# SparkFun_Optical_Tracking_Odometry_Senso.net
KiCad netlist of a schematic drawn in EAGLE
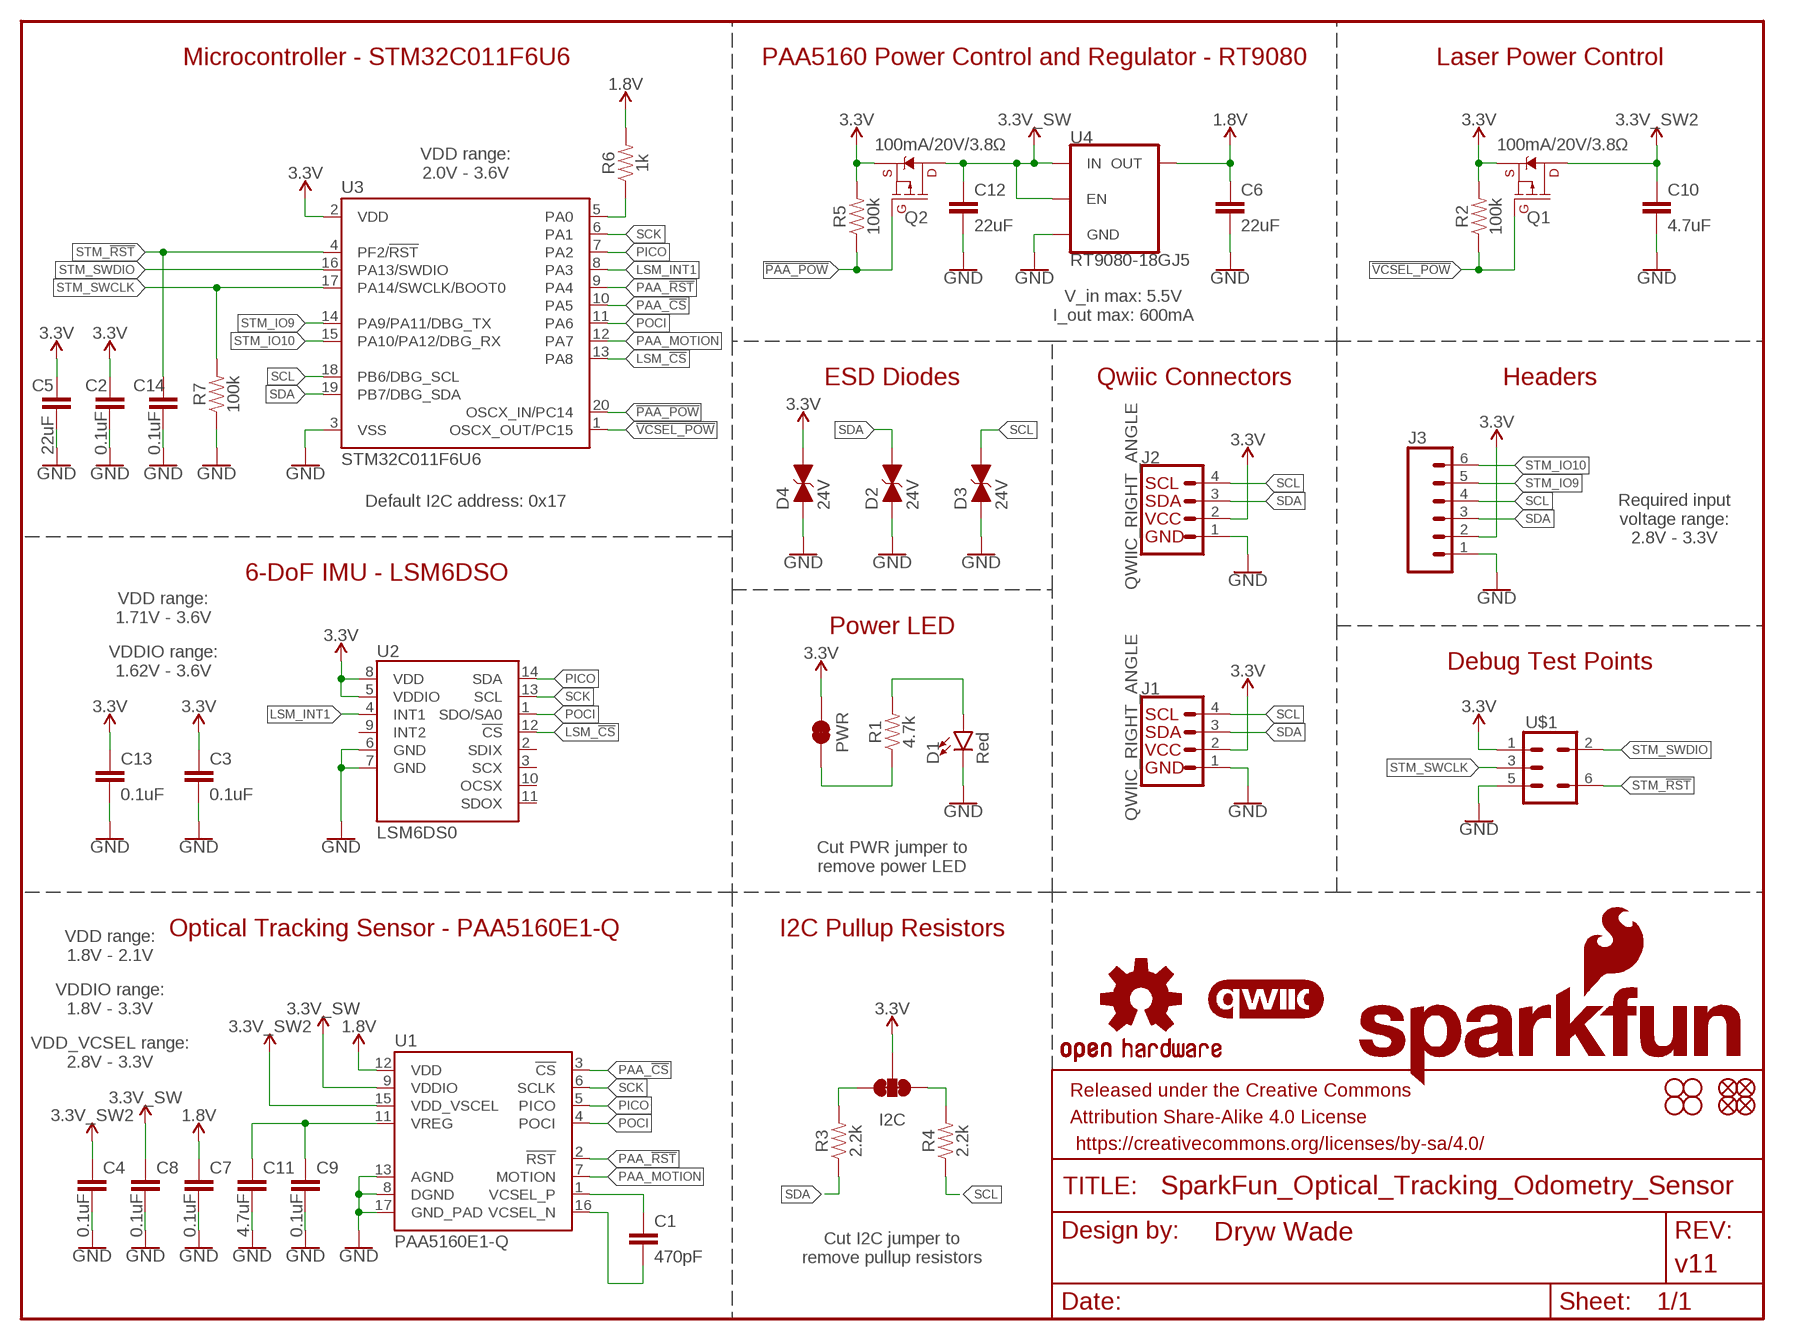
[diagram p0: schematic, sheet 1]

(export (version "E")
  (design (tool "Eeschema 10.0.6"))
  (components
    (comp (ref "C1")
      (value "470pF")
      (footprint "eagle-import:0603")
      (libsource (lib "eagle-import") (part "470PF-0603-50V-5%"))
    )
    (comp (ref "C2")
      (value "0.1uF")
      (footprint "eagle-import:0603")
      (libsource (lib "eagle-import") (part "0.1UF-0603-25V-(+80/-20%)"))
    )
    (comp (ref "C3")
      (value "0.1uF")
      (footprint "eagle-import:0603")
      (libsource (lib "eagle-import") (part "0.1UF-0603-25V-(+80/-20%)"))
    )
    (comp (ref "C4")
      (value "0.1uF")
      (footprint "eagle-import:0603")
      (libsource (lib "eagle-import") (part "0.1UF-0603-25V-(+80/-20%)"))
    )
    (comp (ref "C5")
      (value "22uF")
      (footprint "eagle-import:0603")
      (libsource (lib "eagle-import") (part "22UF-0603-6.3V-20%"))
    )
    (comp (ref "C6")
      (value "22uF")
      (footprint "eagle-import:0603")
      (libsource (lib "eagle-import") (part "22UF-0603-6.3V-20%"))
    )
    (comp (ref "C7")
      (value "0.1uF")
      (footprint "eagle-import:0603")
      (libsource (lib "eagle-import") (part "0.1UF-0603-25V-(+80/-20%)"))
    )
    (comp (ref "C8")
      (value "0.1uF")
      (footprint "eagle-import:0603")
      (libsource (lib "eagle-import") (part "0.1UF-0603-25V-(+80/-20%)"))
    )
    (comp (ref "C9")
      (value "0.1uF")
      (footprint "eagle-import:0603")
      (libsource (lib "eagle-import") (part "0.1UF-0603-25V-(+80/-20%)"))
    )
    (comp (ref "C10")
      (value "4.7uF")
      (footprint "eagle-import:0603")
      (libsource (lib "eagle-import") (part "4.7UF-0603-6.3V-(10%)"))
    )
    (comp (ref "C11")
      (value "4.7uF")
      (footprint "eagle-import:0603")
      (libsource (lib "eagle-import") (part "4.7UF-0603-6.3V-(10%)"))
    )
    (comp (ref "C12")
      (value "22uF")
      (footprint "eagle-import:0603")
      (libsource (lib "eagle-import") (part "22UF-0603-6.3V-20%"))
    )
    (comp (ref "C13")
      (value "0.1uF")
      (footprint "eagle-import:0603")
      (libsource (lib "eagle-import") (part "0.1UF-0603-25V-(+80/-20%)"))
    )
    (comp (ref "C14")
      (value "0.1uF")
      (footprint "eagle-import:0603")
      (libsource (lib "eagle-import") (part "0.1UF-0603-25V-(+80/-20%)"))
    )
    (comp (ref "D1")
      (value "Red")
      (footprint "eagle-import:LED-0603")
      (libsource (lib "eagle-import") (part "LED-RED_0603-KB"))
    )
    (comp (ref "D2")
      (value "24V")
      (footprint "eagle-import:0603")
      (libsource (lib "eagle-import") (part "DIODE_TVS"))
    )
    (comp (ref "D3")
      (value "24V")
      (footprint "eagle-import:0603")
      (libsource (lib "eagle-import") (part "DIODE_TVS"))
    )
    (comp (ref "D4")
      (value "24V")
      (footprint "eagle-import:0603")
      (libsource (lib "eagle-import") (part "DIODE_TVS"))
    )
    (comp (ref "FD1")
      (value "FIDUCIAL1X2")
      (footprint "eagle-import:FIDUCIAL-1X2")
      (libsource (lib "eagle-import") (part "FIDUCIAL1X2"))
    )
    (comp (ref "FD2")
      (value "FIDUCIAL1X2")
      (footprint "eagle-import:FIDUCIAL-1X2")
      (libsource (lib "eagle-import") (part "FIDUCIAL1X2"))
    )
    (comp (ref "FD3")
      (value "FIDUCIAL1X2")
      (footprint "eagle-import:FIDUCIAL-1X2")
      (libsource (lib "eagle-import") (part "FIDUCIAL1X2"))
    )
    (comp (ref "FD4")
      (value "FIDUCIAL1X2")
      (footprint "eagle-import:FIDUCIAL-1X2")
      (libsource (lib "eagle-import") (part "FIDUCIAL1X2"))
    )
    (comp (ref "FRAME1")
      (value "FRAME-LETTER")
      (footprint "eagle-import:CREATIVE_COMMONS")
      (fields (field (name "DESIGNER") "Dryw Wade") (field (name "REV") "v11"))
      (libsource (lib "eagle-import") (part "FRAME-LETTER"))
    )
    (comp (ref "H1")
      (value "STAND-OFF")
      (footprint "eagle-import:STAND-OFF")
      (libsource (lib "eagle-import") (part "STAND-OFF"))
    )
    (comp (ref "H2")
      (value "STAND-OFF")
      (footprint "eagle-import:STAND-OFF")
      (libsource (lib "eagle-import") (part "STAND-OFF"))
    )
    (comp (ref "H3")
      (value "STAND-OFF")
      (footprint "eagle-import:STAND-OFF")
      (libsource (lib "eagle-import") (part "STAND-OFF"))
    )
    (comp (ref "H4")
      (value "STAND-OFF")
      (footprint "eagle-import:STAND-OFF")
      (libsource (lib "eagle-import") (part "STAND-OFF"))
    )
    (comp (ref "I2C")
      (value "JUMPER-SMT_3_2-NC_TRACE_SILK")
      (footprint "eagle-import:SMT-JUMPER_3_2-NC_TRACE_SILK")
      (libsource (lib "eagle-import") (part "JUMPER-SMT_3_2-NC_TRACE_SILK"))
    )
    (comp (ref "J1")
      (value "QWIIC_RIGHT_ANGLE")
      (footprint "eagle-import:JST04_1MM_RA")
      (libsource (lib "eagle-import") (part "QWIIC_CONNECTORJS-1MM"))
    )
    (comp (ref "J2")
      (value "QWIIC_RIGHT_ANGLE")
      (footprint "eagle-import:JST04_1MM_RA")
      (libsource (lib "eagle-import") (part "QWIIC_CONNECTORJS-1MM"))
    )
    (comp (ref "J3")
      (value "CONN_06NO_SILK_NO_POP")
      (footprint "eagle-import:1X06_NO_SILK")
      (libsource (lib "eagle-import") (part "CONN_06NO_SILK_NO_POP"))
    )
    (comp (ref "LOGO1")
      (value "OSHW-LOGOS")
      (footprint "eagle-import:OSHW-LOGO-S")
      (libsource (lib "eagle-import") (part "OSHW-LOGOS"))
    )
    (comp (ref "LOGO2")
      (value "QWIIC_LOGO_5MM")
      (footprint "eagle-import:QWIIC_5MM")
      (libsource (lib "eagle-import") (part "QWIIC_LOGO_5MM"))
    )
    (comp (ref "LOGO3")
      (value "SFE_LOGO_NAME_FLAME.1_INCH")
      (footprint "eagle-import:SFE_LOGO_NAME_FLAME_.1")
      (libsource (lib "eagle-import") (part "SFE_LOGO_NAME_FLAME.1_INCH"))
    )
    (comp (ref "PWR")
      (value "JUMPER-SMT_2_NC_TRACE_SILK")
      (footprint "eagle-import:SMT-JUMPER_2_NC_TRACE_SILK")
      (libsource (lib "eagle-import") (part "JUMPER-SMT_2_NC_TRACE_SILK"))
    )
    (comp (ref "Q1")
      (value "100mA/20V/3.8Ω")
      (footprint "eagle-import:SOT-416FL")
      (libsource (lib "eagle-import") (part "MOSFET_PCH-RE1C001ZPTL"))
    )
    (comp (ref "Q2")
      (value "100mA/20V/3.8Ω")
      (footprint "eagle-import:SOT-416FL")
      (libsource (lib "eagle-import") (part "MOSFET_PCH-RE1C001ZPTL"))
    )
    (comp (ref "R1")
      (value "4.7k")
      (footprint "eagle-import:0603")
      (libsource (lib "eagle-import") (part "4.7KOHM-0603-1/10W-1%"))
    )
    (comp (ref "R2")
      (value "100k")
      (footprint "eagle-import:0603")
      (libsource (lib "eagle-import") (part "100KOHM-0603-1/10W-1%"))
    )
    (comp (ref "R3")
      (value "2.2k")
      (footprint "eagle-import:0603")
      (libsource (lib "eagle-import") (part "2.2KOHM-0603-1/10W-1%"))
    )
    (comp (ref "R4")
      (value "2.2k")
      (footprint "eagle-import:0603")
      (libsource (lib "eagle-import") (part "2.2KOHM-0603-1/10W-1%"))
    )
    (comp (ref "R5")
      (value "100k")
      (footprint "eagle-import:0603")
      (libsource (lib "eagle-import") (part "100KOHM-0603-1/10W-1%"))
    )
    (comp (ref "R6")
      (value "1k")
      (footprint "eagle-import:0603")
      (libsource (lib "eagle-import") (part "1KOHM-0603-1/10W-1%"))
    )
    (comp (ref "R7")
      (value "100k")
      (footprint "eagle-import:0603")
      (libsource (lib "eagle-import") (part "100KOHM-0603-1/10W-1%"))
    )
    (comp (ref "U$1")
      (value "SWD-5PIN")
      (footprint "eagle-import:PAD_05_03X2_TP_NO4")
      (libsource (lib "eagle-import") (part "SWD-5PIN"))
    )
    (comp (ref "U1")
      (value "PAA5160E1-Q")
      (footprint "eagle-import:PAA5160E1-Q")
      (libsource (lib "eagle-import") (part "PAA5160E1-Q"))
    )
    (comp (ref "U2")
      (value "LSM6DS0")
      (footprint "eagle-import:LGA14L")
      (libsource (lib "eagle-import") (part "LSM6DSO"))
    )
    (comp (ref "U3")
      (value "STM32C011F6U6")
      (footprint "eagle-import:STM32C011F6U6")
      (libsource (lib "eagle-import") (part "STM32C011F6U6"))
    )
    (comp (ref "U4")
      (value "RT9080-18GJ5")
      (footprint "eagle-import:SOT23-5")
      (libsource (lib "eagle-import") (part "V_REG_RT9080-18GJ5"))
    )
  )
  (nets
    (net (code "1") (name "/LSM_~{CS}") (class "Default")
      (node (ref "U2") (pin "12") (pinfunction "~{CS}_12") (pintype "bidirectional"))
      (node (ref "U3") (pin "13") (pinfunction "PA8_13") (pintype "bidirectional"))
    )
    (net (code "2") (name "/PAA_~{CS}") (class "Default")
      (node (ref "U1") (pin "3") (pinfunction "~{CS}_3") (pintype "bidirectional"))
      (node (ref "U3") (pin "10") (pinfunction "PA5_10") (pintype "bidirectional"))
    )
    (net (code "3") (name "/PAA_~{RST}") (class "Default")
      (node (ref "U1") (pin "2") (pinfunction "~{RST}_2") (pintype "bidirectional"))
      (node (ref "U3") (pin "9") (pinfunction "PA4_9") (pintype "bidirectional"))
    )
    (net (code "4") (name "/STM_~{RST}") (class "Default")
      (node (ref "C14") (pin "1") (pinfunction "1_1") (pintype "passive"))
      (node (ref "U$1") (pin "6") (pinfunction "6_6") (pintype "bidirectional"))
      (node (ref "U3") (pin "4") (pinfunction "PF2/~{RST}_4") (pintype "bidirectional"))
    )
    (net (code "5") (name "/~{PAA_POW}") (class "Default")
      (node (ref "Q2") (pin "1") (pinfunction "G_1") (pintype "bidirectional"))
      (node (ref "R5") (pin "1") (pinfunction "1_1") (pintype "passive"))
      (node (ref "U3") (pin "20") (pinfunction "OSCX_IN/PC14_20") (pintype "bidirectional"))
    )
    (net (code "6") (name "/~{VCSEL_POW}") (class "Default")
      (node (ref "Q1") (pin "1") (pinfunction "G_1") (pintype "bidirectional"))
      (node (ref "R2") (pin "1") (pinfunction "1_1") (pintype "passive"))
      (node (ref "U3") (pin "1") (pinfunction "OSCX_OUT/PC15_1") (pintype "bidirectional"))
    )
    (net (code "7") (name "1.8V") (class "Default")
      (node (ref "C6") (pin "1") (pinfunction "1_1") (pintype "passive"))
      (node (ref "C7") (pin "1") (pinfunction "1_1") (pintype "passive"))
      (node (ref "R6") (pin "2") (pinfunction "2_2") (pintype "passive"))
      (node (ref "U1") (pin "12") (pinfunction "VDD_12") (pintype "bidirectional"))
      (node (ref "U4") (pin "5") (pinfunction "OUT_5") (pintype "passive"))
    )
    (net (code "8") (name "3.3V") (class "Default")
      (node (ref "C13") (pin "1") (pinfunction "1_1") (pintype "passive"))
      (node (ref "C2") (pin "1") (pinfunction "1_1") (pintype "passive"))
      (node (ref "C3") (pin "1") (pinfunction "1_1") (pintype "passive"))
      (node (ref "C5") (pin "1") (pinfunction "1_1") (pintype "passive"))
      (node (ref "D4") (pin "2") (pinfunction "C_2") (pintype "passive"))
      (node (ref "I2C") (pin "2") (pinfunction "2_2") (pintype "passive"))
      (node (ref "J1") (pin "2") (pinfunction "2_2") (pintype "power_in"))
      (node (ref "J2") (pin "2") (pinfunction "2_2") (pintype "power_in"))
      (node (ref "J3") (pin "2") (pinfunction "2_2") (pintype "passive"))
      (node (ref "PWR") (pin "2") (pinfunction "2_2") (pintype "passive"))
      (node (ref "Q1") (pin "2") (pinfunction "S_2") (pintype "bidirectional"))
      (node (ref "Q2") (pin "2") (pinfunction "S_2") (pintype "bidirectional"))
      (node (ref "R2") (pin "2") (pinfunction "2_2") (pintype "passive"))
      (node (ref "R5") (pin "2") (pinfunction "2_2") (pintype "passive"))
      (node (ref "U$1") (pin "1") (pinfunction "1_1") (pintype "bidirectional"))
      (node (ref "U2") (pin "5") (pinfunction "VDDIO_5") (pintype "bidirectional"))
      (node (ref "U2") (pin "8") (pinfunction "VDD_8") (pintype "bidirectional"))
      (node (ref "U3") (pin "2") (pinfunction "VDD_2") (pintype "bidirectional"))
    )
    (net (code "9") (name "3.3V_SW") (class "Default")
      (node (ref "C12") (pin "1") (pinfunction "1_1") (pintype "passive"))
      (node (ref "C8") (pin "1") (pinfunction "1_1") (pintype "passive"))
      (node (ref "Q2") (pin "3") (pinfunction "D_3") (pintype "bidirectional"))
      (node (ref "U1") (pin "9") (pinfunction "VDDIO_9") (pintype "bidirectional"))
      (node (ref "U4") (pin "1") (pinfunction "IN_1") (pintype "input"))
      (node (ref "U4") (pin "3") (pinfunction "EN_3") (pintype "input"))
    )
    (net (code "10") (name "3.3V_SW2") (class "Default")
      (node (ref "C10") (pin "1") (pinfunction "1_1") (pintype "passive"))
      (node (ref "C4") (pin "1") (pinfunction "1_1") (pintype "passive"))
      (node (ref "Q1") (pin "3") (pinfunction "D_3") (pintype "bidirectional"))
      (node (ref "U1") (pin "15") (pinfunction "VDD_VSCEL_15") (pintype "bidirectional"))
    )
    (net (code "11") (name "GND") (class "Default")
      (node (ref "C10") (pin "2") (pinfunction "2_2") (pintype "passive"))
      (node (ref "C11") (pin "2") (pinfunction "2_2") (pintype "passive"))
      (node (ref "C12") (pin "2") (pinfunction "2_2") (pintype "passive"))
      (node (ref "C13") (pin "2") (pinfunction "2_2") (pintype "passive"))
      (node (ref "C14") (pin "2") (pinfunction "2_2") (pintype "passive"))
      (node (ref "C2") (pin "2") (pinfunction "2_2") (pintype "passive"))
      (node (ref "C3") (pin "2") (pinfunction "2_2") (pintype "passive"))
      (node (ref "C4") (pin "2") (pinfunction "2_2") (pintype "passive"))
      (node (ref "C5") (pin "2") (pinfunction "2_2") (pintype "passive"))
      (node (ref "C6") (pin "2") (pinfunction "2_2") (pintype "passive"))
      (node (ref "C7") (pin "2") (pinfunction "2_2") (pintype "passive"))
      (node (ref "C8") (pin "2") (pinfunction "2_2") (pintype "passive"))
      (node (ref "C9") (pin "2") (pinfunction "2_2") (pintype "passive"))
      (node (ref "D1") (pin "C") (pinfunction "C_C") (pintype "passive"))
      (node (ref "D2") (pin "1") (pinfunction "A_1") (pintype "passive"))
      (node (ref "D3") (pin "1") (pinfunction "A_1") (pintype "passive"))
      (node (ref "D4") (pin "1") (pinfunction "A_1") (pintype "passive"))
      (node (ref "J1") (pin "1") (pinfunction "1_1") (pintype "power_in"))
      (node (ref "J2") (pin "1") (pinfunction "1_1") (pintype "power_in"))
      (node (ref "J3") (pin "1") (pinfunction "1_1") (pintype "passive"))
      (node (ref "R7") (pin "1") (pinfunction "1_1") (pintype "passive"))
      (node (ref "U$1") (pin "5") (pinfunction "5_5") (pintype "bidirectional"))
      (node (ref "U1") (pin "13") (pinfunction "AGND_13") (pintype "bidirectional"))
      (node (ref "U1") (pin "17") (pinfunction "GND_PAD_17") (pintype "bidirectional"))
      (node (ref "U1") (pin "8") (pinfunction "DGND_8") (pintype "bidirectional"))
      (node (ref "U2") (pin "6") (pinfunction "GND_6") (pintype "bidirectional"))
      (node (ref "U2") (pin "7") (pinfunction "GND_7") (pintype "bidirectional"))
      (node (ref "U3") (pin "3") (pinfunction "VSS_3") (pintype "bidirectional"))
      (node (ref "U4") (pin "2") (pinfunction "GND_2") (pintype "input"))
    )
    (net (code "12") (name "LSM_INT1") (class "Default")
      (node (ref "U2") (pin "4") (pinfunction "INT1_4") (pintype "bidirectional"))
      (node (ref "U3") (pin "8") (pinfunction "PA3_8") (pintype "bidirectional"))
    )
    (net (code "13") (name "Net-(D1-PadA)") (class "Default")
      (node (ref "D1") (pin "A") (pinfunction "A_A") (pintype "passive"))
      (node (ref "R1") (pin "2") (pinfunction "2_2") (pintype "passive"))
    )
    (net (code "14") (name "Net-(I2C-Pad1)") (class "Default")
      (node (ref "I2C") (pin "1") (pinfunction "1_1") (pintype "passive"))
      (node (ref "R4") (pin "2") (pinfunction "2_2") (pintype "passive"))
    )
    (net (code "15") (name "Net-(I2C-Pad3)") (class "Default")
      (node (ref "I2C") (pin "3") (pinfunction "3_3") (pintype "passive"))
      (node (ref "R3") (pin "2") (pinfunction "2_2") (pintype "passive"))
    )
    (net (code "16") (name "Net-(PWR-Pad1)") (class "Default")
      (node (ref "PWR") (pin "1") (pinfunction "1_1") (pintype "passive"))
      (node (ref "R1") (pin "1") (pinfunction "1_1") (pintype "passive"))
    )
    (net (code "17") (name "Net-(U1-VCSEL_N)") (class "Default")
      (node (ref "C1") (pin "2") (pinfunction "2_2") (pintype "passive"))
      (node (ref "U1") (pin "16") (pinfunction "VCSEL_N_16") (pintype "bidirectional"))
    )
    (net (code "18") (name "Net-(U1-VCSEL_P)") (class "Default")
      (node (ref "C1") (pin "1") (pinfunction "1_1") (pintype "passive"))
      (node (ref "U1") (pin "1") (pinfunction "VCSEL_P_1") (pintype "bidirectional"))
    )
    (net (code "19") (name "Net-(U1-VREG)") (class "Default")
      (node (ref "C11") (pin "1") (pinfunction "1_1") (pintype "passive"))
      (node (ref "C9") (pin "1") (pinfunction "1_1") (pintype "passive"))
      (node (ref "U1") (pin "11") (pinfunction "VREG_11") (pintype "bidirectional"))
    )
    (net (code "20") (name "Net-(U3-PA0)") (class "Default")
      (node (ref "R6") (pin "1") (pinfunction "1_1") (pintype "passive"))
      (node (ref "U3") (pin "5") (pinfunction "PA0_5") (pintype "bidirectional"))
    )
    (net (code "21") (name "PAA_MOTION") (class "Default")
      (node (ref "U1") (pin "7") (pinfunction "MOTION_7") (pintype "bidirectional"))
      (node (ref "U3") (pin "12") (pinfunction "PA7_12") (pintype "bidirectional"))
    )
    (net (code "22") (name "PICO") (class "Default")
      (node (ref "U1") (pin "5") (pinfunction "PICO_5") (pintype "bidirectional"))
      (node (ref "U2") (pin "14") (pinfunction "SDA_14") (pintype "bidirectional"))
      (node (ref "U3") (pin "7") (pinfunction "PA2_7") (pintype "bidirectional"))
    )
    (net (code "23") (name "POCI") (class "Default")
      (node (ref "U1") (pin "4") (pinfunction "POCI_4") (pintype "bidirectional"))
      (node (ref "U2") (pin "1") (pinfunction "SDO/SA0_1") (pintype "bidirectional"))
      (node (ref "U3") (pin "11") (pinfunction "PA6_11") (pintype "bidirectional"))
    )
    (net (code "24") (name "SCK") (class "Default")
      (node (ref "U1") (pin "6") (pinfunction "SCLK_6") (pintype "bidirectional"))
      (node (ref "U2") (pin "13") (pinfunction "SCL_13") (pintype "bidirectional"))
      (node (ref "U3") (pin "6") (pinfunction "PA1_6") (pintype "bidirectional"))
    )
    (net (code "25") (name "SCL") (class "Default")
      (node (ref "D3") (pin "2") (pinfunction "C_2") (pintype "passive"))
      (node (ref "J1") (pin "4") (pinfunction "4_4") (pintype "passive"))
      (node (ref "J2") (pin "4") (pinfunction "4_4") (pintype "passive"))
      (node (ref "J3") (pin "4") (pinfunction "4_4") (pintype "passive"))
      (node (ref "R4") (pin "1") (pinfunction "1_1") (pintype "passive"))
      (node (ref "U3") (pin "18") (pinfunction "PB6/DBG_SCL_18") (pintype "bidirectional"))
    )
    (net (code "26") (name "SDA") (class "Default")
      (node (ref "D2") (pin "2") (pinfunction "C_2") (pintype "passive"))
      (node (ref "J1") (pin "3") (pinfunction "3_3") (pintype "passive"))
      (node (ref "J2") (pin "3") (pinfunction "3_3") (pintype "passive"))
      (node (ref "J3") (pin "3") (pinfunction "3_3") (pintype "passive"))
      (node (ref "R3") (pin "1") (pinfunction "1_1") (pintype "passive"))
      (node (ref "U3") (pin "19") (pinfunction "PB7/DBG_SDA_19") (pintype "bidirectional"))
    )
    (net (code "27") (name "STM_IO9") (class "Default")
      (node (ref "J3") (pin "5") (pinfunction "5_5") (pintype "passive"))
      (node (ref "U3") (pin "14") (pinfunction "PA9/PA11/DBG_TX_14") (pintype "bidirectional"))
    )
    (net (code "28") (name "STM_IO10") (class "Default")
      (node (ref "J3") (pin "6") (pinfunction "6_6") (pintype "passive"))
      (node (ref "U3") (pin "15") (pinfunction "PA10/PA12/DBG_RX_15") (pintype "bidirectional"))
    )
    (net (code "29") (name "STM_SWCLK") (class "Default")
      (node (ref "R7") (pin "2") (pinfunction "2_2") (pintype "passive"))
      (node (ref "U$1") (pin "3") (pinfunction "3_3") (pintype "bidirectional"))
      (node (ref "U3") (pin "17") (pinfunction "PA14/SWCLK/BOOT0_17") (pintype "bidirectional"))
    )
    (net (code "30") (name "STM_SWDIO") (class "Default")
      (node (ref "U$1") (pin "2") (pinfunction "2_2") (pintype "bidirectional"))
      (node (ref "U3") (pin "16") (pinfunction "PA13/SWDIO_16") (pintype "bidirectional"))
    )
    (net (code "31") (name "unconnected-(U2-INT2-Pad9)") (class "Default")
      (node (ref "U2") (pin "9") (pinfunction "INT2_9") (pintype "bidirectional"))
    )
    (net (code "32") (name "unconnected-(U2-OCSX-Pad10)") (class "Default")
      (node (ref "U2") (pin "10") (pinfunction "OCSX_10") (pintype "bidirectional"))
    )
    (net (code "33") (name "unconnected-(U2-SCX-Pad3)") (class "Default")
      (node (ref "U2") (pin "3") (pinfunction "SCX_3") (pintype "bidirectional"))
    )
    (net (code "34") (name "unconnected-(U2-SDIX-Pad2)") (class "Default")
      (node (ref "U2") (pin "2") (pinfunction "SDIX_2") (pintype "bidirectional"))
    )
    (net (code "35") (name "unconnected-(U2-SDOX-Pad11)") (class "Default")
      (node (ref "U2") (pin "11") (pinfunction "SDOX_11") (pintype "bidirectional"))
    )
  )
)
